# X16-Pi-Shield.net
KiCad netlist of a schematic drawn in EAGLE
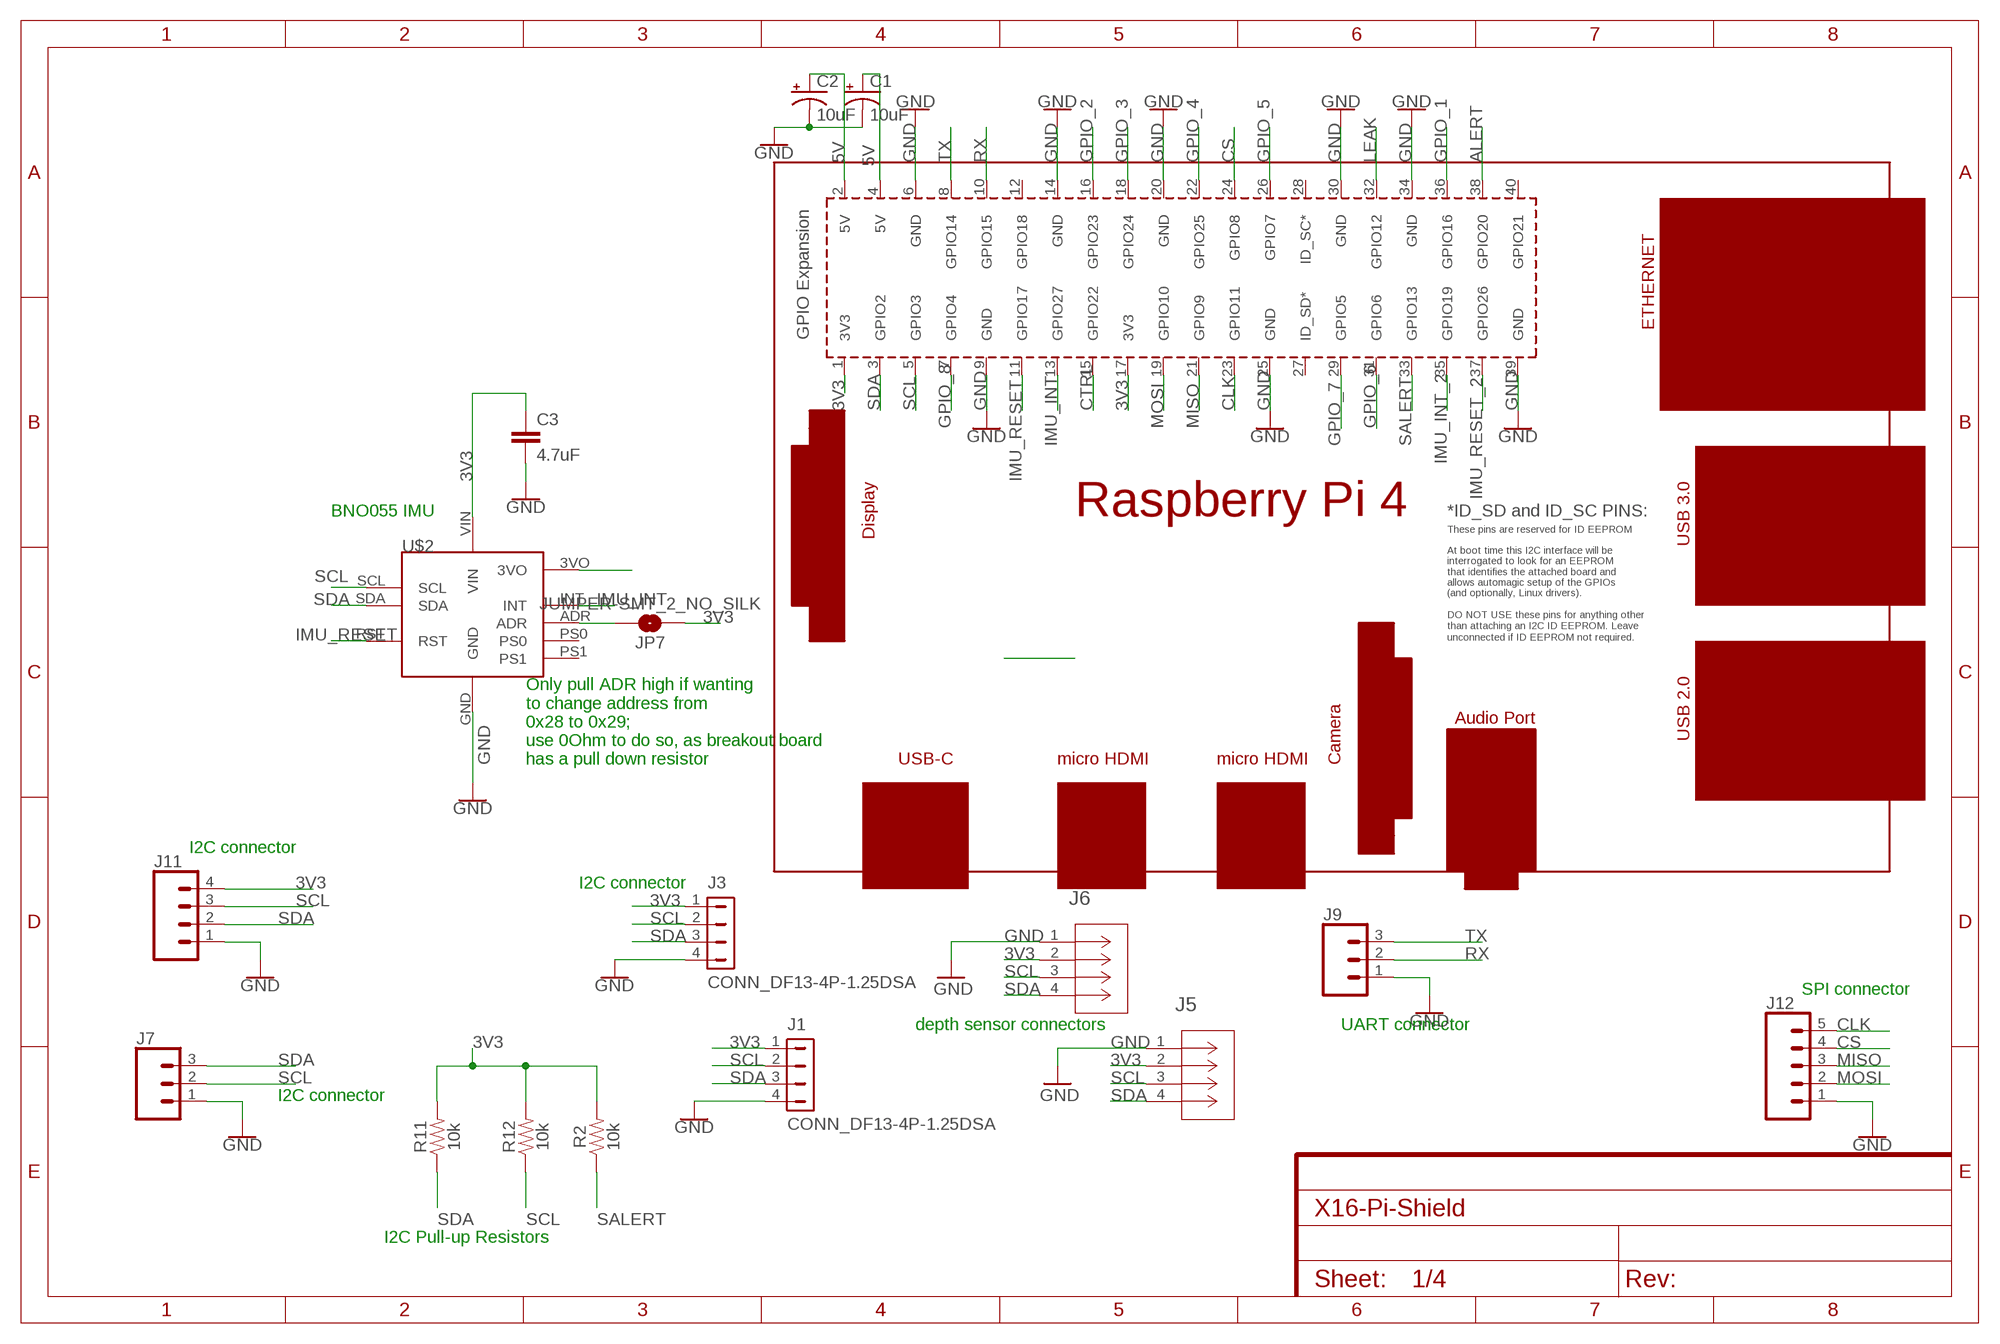
[diagram p0: schematic, sheet 1]
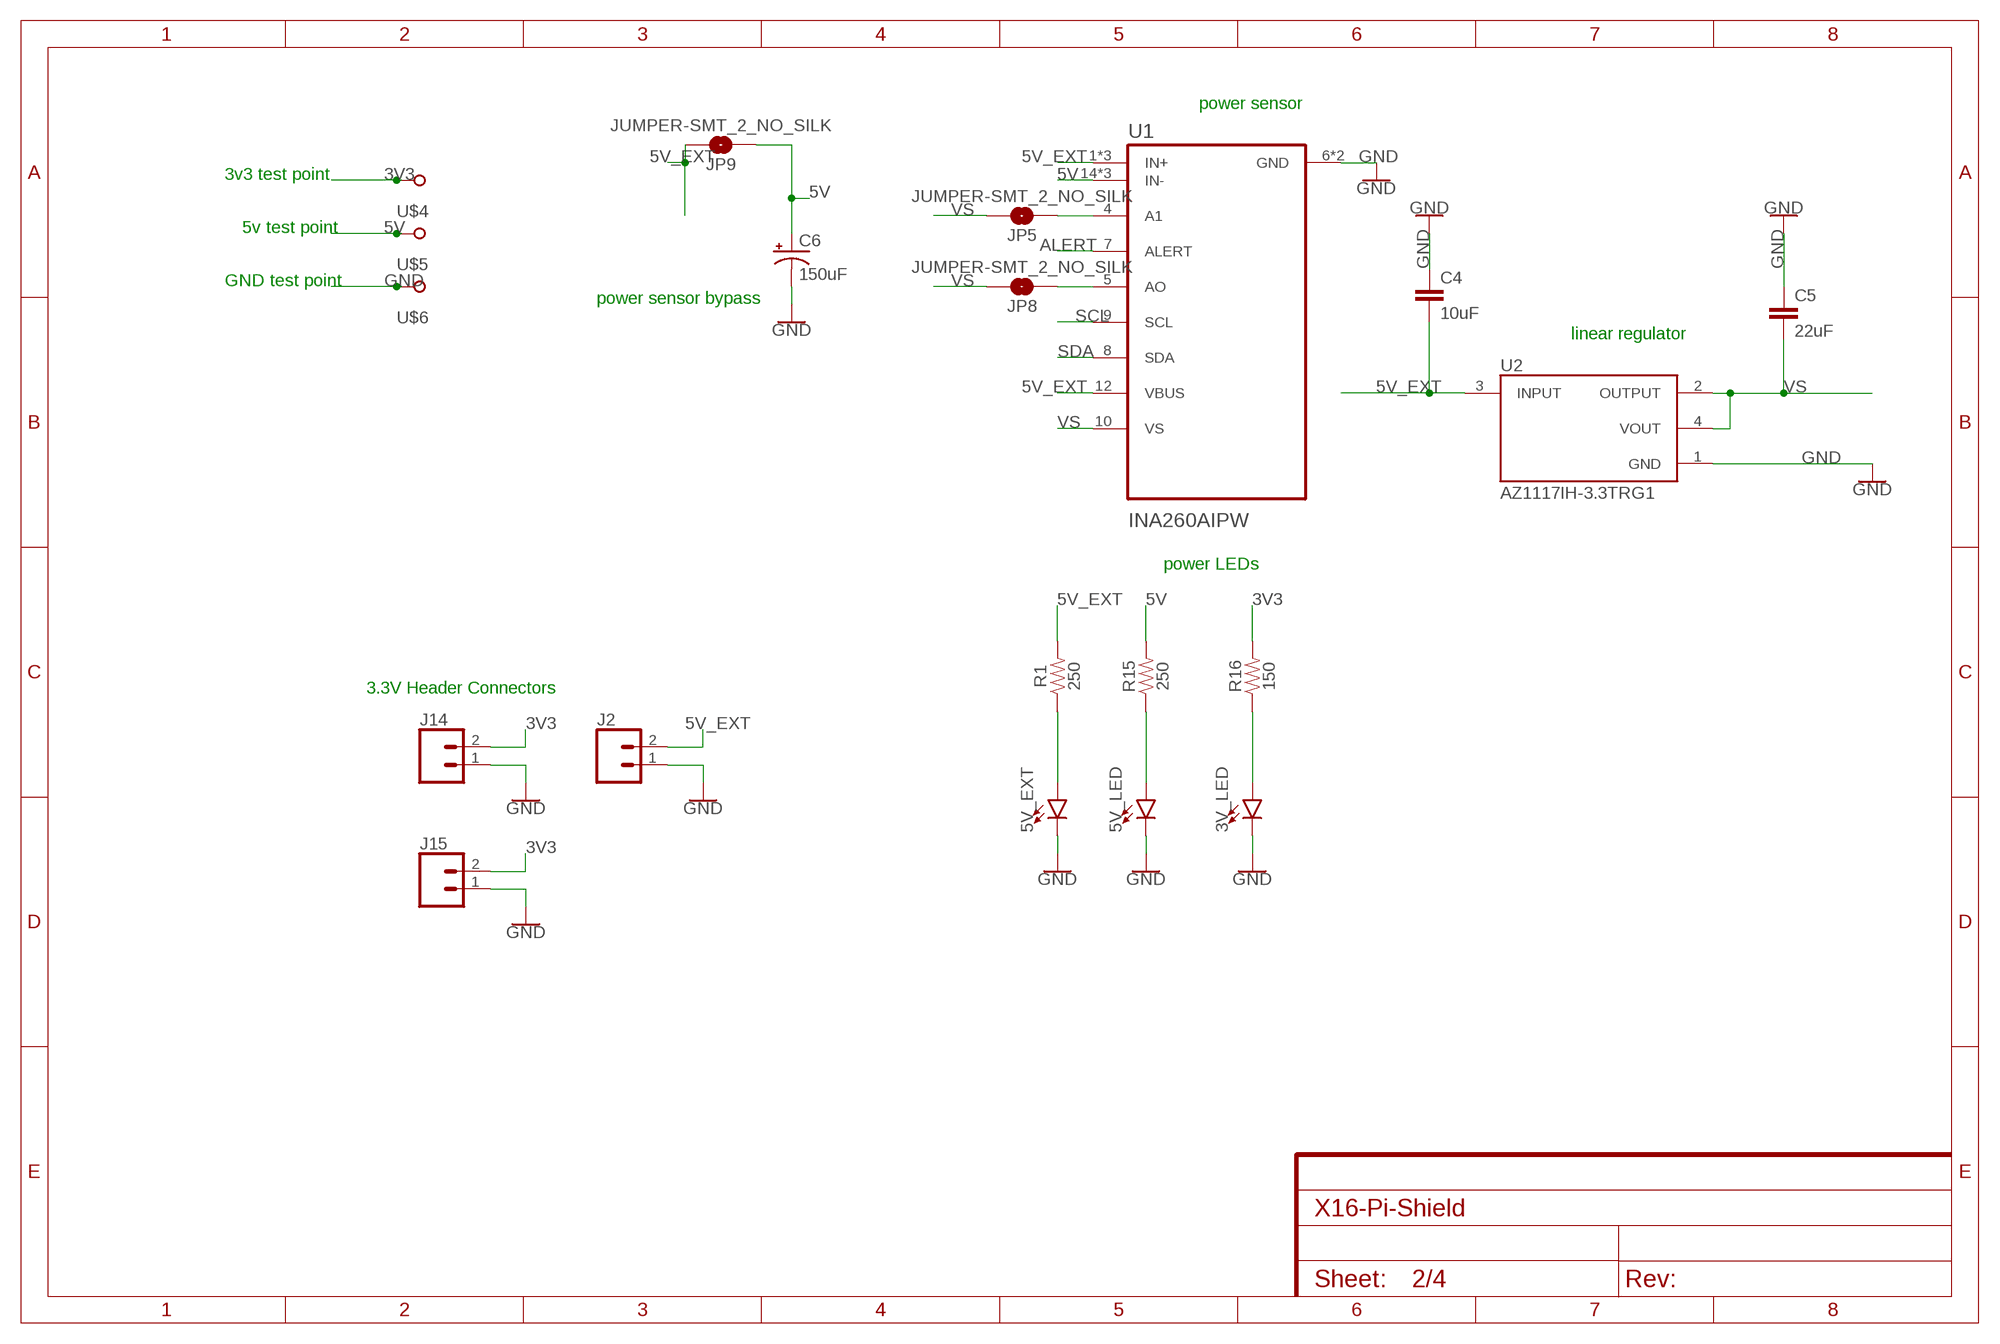
[diagram p1: schematic, sheet 2]
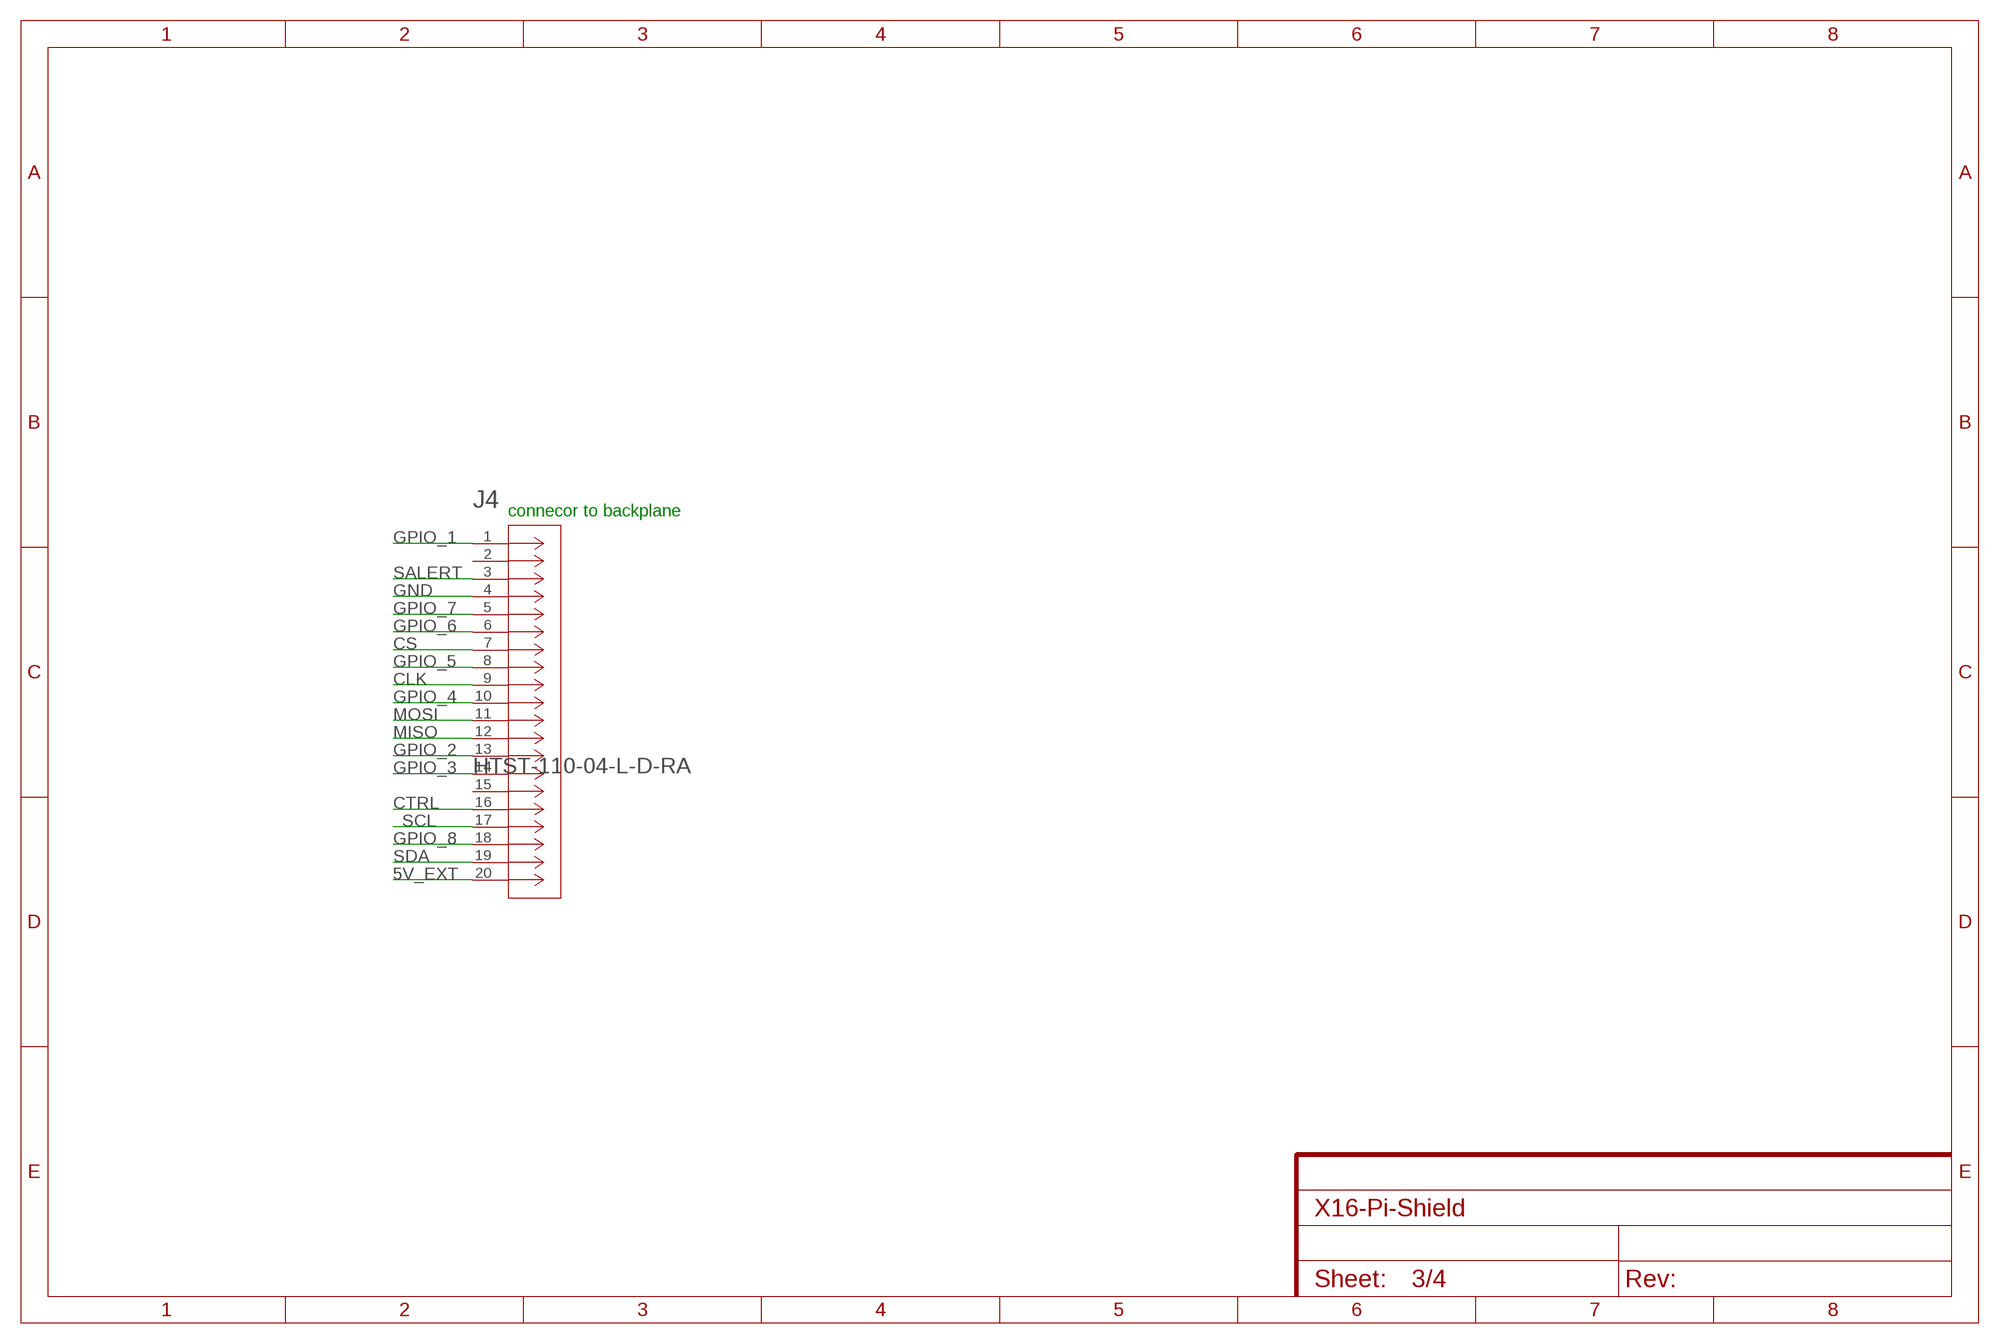
[diagram p2: schematic, sheet 3]
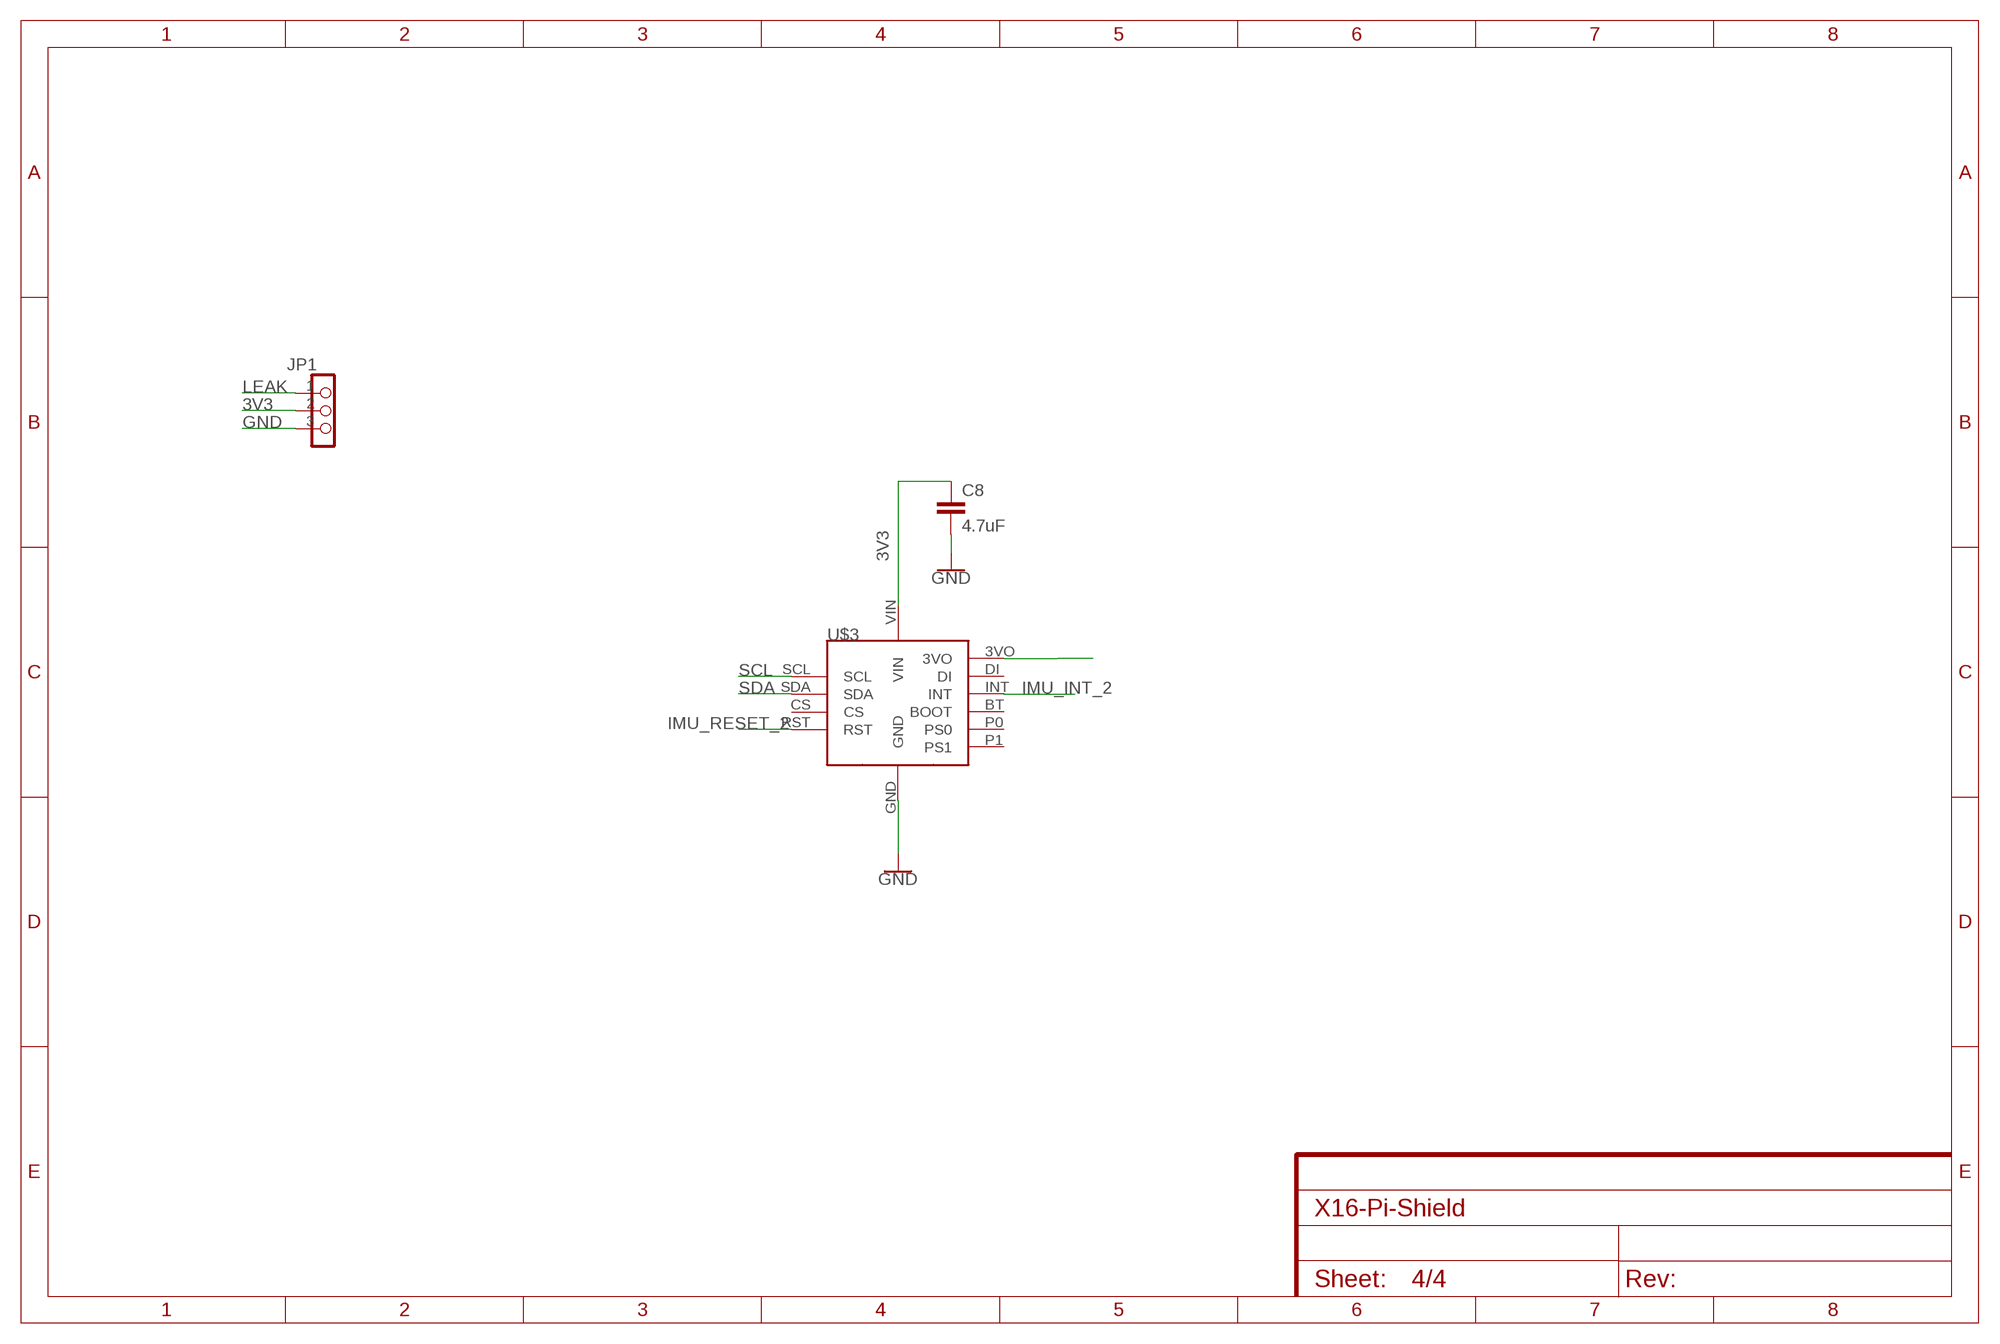
[diagram p3: schematic, sheet 4]

(export (version "E")
  (design (tool "Eeschema 10.0.6"))
  (components
    (comp (ref "J4")
      (value "HTST-110-04-L-D-RA")
      (footprint "eagle-import:CONN_HTST-110-04_05-X-D-RA_SAI")
      (fields (field (name "COPYRIGHT") "Copyright (C) 2023 Ultra Librarian. All rights reserved."))
      (libsource (lib "eagle-import") (part "HTST-110-04-L-D-RA"))
    )
    (comp (ref "C8")
      (value "4.7uF")
      (footprint "eagle-import:0603")
      (libsource (lib "eagle-import") (part "4.7UF0603"))
    )
    (comp (ref "JP1")
      (value "TEST_PIN-1X3")
      (footprint "eagle-import:1X03")
      (libsource (lib "eagle-import") (part "TEST_PIN-1X3"))
    )
    (comp (ref "U$3")
      (value "ADAFRUIT-BNO080")
      (footprint "eagle-import:ADAFRUIT-BNO080")
      (libsource (lib "eagle-import") (part "ADAFRUIT-BNO080"))
    )
    (comp (ref "3V_LED")
      (value "LEDCHIPLED_0805")
      (footprint "eagle-import:CHIPLED_0805")
      (libsource (lib "eagle-import") (part "LEDCHIPLED_0805"))
    )
    (comp (ref "5V_EXT")
      (value "LEDCHIPLED_0805")
      (footprint "eagle-import:CHIPLED_0805")
      (libsource (lib "eagle-import") (part "LEDCHIPLED_0805"))
    )
    (comp (ref "5V_LED")
      (value "LEDCHIPLED_0805")
      (footprint "eagle-import:CHIPLED_0805")
      (libsource (lib "eagle-import") (part "LEDCHIPLED_0805"))
    )
    (comp (ref "C4")
      (value "10uF")
      (footprint "eagle-import:0603")
      (libsource (lib "eagle-import") (part "2.2UF-0603-10V-20%"))
    )
    (comp (ref "C5")
      (value "22uF")
      (footprint "eagle-import:0603")
      (libsource (lib "eagle-import") (part "2.2UF-0603-10V-20%"))
    )
    (comp (ref "C6")
      (value "150uF")
      (footprint "eagle-import:2917(7343-31-METRIC)")
      (libsource (lib "eagle-import") (part "C-TANTALUM(10UF_150UF)"))
    )
    (comp (ref "J2")
      (value "CONN_02")
      (footprint "eagle-import:1X02")
      (libsource (lib "eagle-import") (part "CONN_02"))
    )
    (comp (ref "J14")
      (value "CONN_02")
      (footprint "eagle-import:1X02")
      (libsource (lib "eagle-import") (part "CONN_02"))
    )
    (comp (ref "J15")
      (value "CONN_02")
      (footprint "eagle-import:1X02")
      (libsource (lib "eagle-import") (part "CONN_02"))
    )
    (comp (ref "JP5")
      (value "JUMPER-SMT_2_NO_SILK")
      (footprint "eagle-import:SMT-JUMPER_2_NO_SILK")
      (libsource (lib "eagle-import") (part "JUMPER-SMT_2_NO_SILK"))
    )
    (comp (ref "JP8")
      (value "JUMPER-SMT_2_NO_SILK")
      (footprint "eagle-import:SMT-JUMPER_2_NO_SILK")
      (libsource (lib "eagle-import") (part "JUMPER-SMT_2_NO_SILK"))
    )
    (comp (ref "JP9")
      (value "JUMPER-SMT_2_NO_SILK")
      (footprint "eagle-import:SMT-JUMPER_2_NO_SILK")
      (libsource (lib "eagle-import") (part "JUMPER-SMT_2_NO_SILK"))
    )
    (comp (ref "R1")
      (value "250")
      (footprint "eagle-import:0603")
      (libsource (lib "eagle-import") (part "RESISTOR0603"))
    )
    (comp (ref "R15")
      (value "250")
      (footprint "eagle-import:0603")
      (libsource (lib "eagle-import") (part "RESISTOR0603"))
    )
    (comp (ref "R16")
      (value "150")
      (footprint "eagle-import:0603")
      (libsource (lib "eagle-import") (part "RESISTOR0603"))
    )
    (comp (ref "U$4")
      (value "TESTPOINT_5.04MM")
      (footprint "eagle-import:TESTPOINT_5.04MM")
      (libsource (lib "eagle-import") (part "TESTPOINT_5.04MM"))
    )
    (comp (ref "U$5")
      (value "TESTPOINT_5.04MM")
      (footprint "eagle-import:TESTPOINT_5.04MM")
      (libsource (lib "eagle-import") (part "TESTPOINT_5.04MM"))
    )
    (comp (ref "U$6")
      (value "TESTPOINT_5.04MM")
      (footprint "eagle-import:TESTPOINT_5.04MM")
      (libsource (lib "eagle-import") (part "TESTPOINT_5.04MM"))
    )
    (comp (ref "U1")
      (value "INA260AIPW")
      (footprint "eagle-import:SOP65P640X120-16N")
      (libsource (lib "eagle-import") (part "INA260AIPW"))
    )
    (comp (ref "U2")
      (value "AZ1117IH-3.3TRG1")
      (footprint "eagle-import:SOT230P700X185-4N")
      (fields (field (name "MANUFACTURER") "Diodes Inc."))
      (libsource (lib "eagle-import") (part "AZ1117IH-3.3TRG1"))
    )
    (comp (ref "C1")
      (value "10uF")
      (footprint "eagle-import:0603-POLAR")
      (libsource (lib "eagle-import") (part "10UF-POLAR-0603-6.3V-20%(TANT)"))
    )
    (comp (ref "C2")
      (value "10uF")
      (footprint "eagle-import:0603-POLAR")
      (libsource (lib "eagle-import") (part "10UF-POLAR-0603-6.3V-20%(TANT)"))
    )
    (comp (ref "C3")
      (value "4.7uF")
      (footprint "eagle-import:0603")
      (libsource (lib "eagle-import") (part "4.7UF0603"))
    )
    (comp (ref "J1")
      (value "CONN_DF13-4P-1.25DSA")
      (footprint "eagle-import:DF13-4P-1.25DSA")
      (libsource (lib "eagle-import") (part "CONN_DF13-4P-1.25DSA"))
    )
    (comp (ref "J3")
      (value "CONN_DF13-4P-1.25DSA")
      (footprint "eagle-import:DF13-4P-1.25DSA")
      (libsource (lib "eagle-import") (part "CONN_DF13-4P-1.25DSA"))
    )
    (comp (ref "J5")
      (value "BM04B-GHS-TBT")
      (footprint "eagle-import:CONN_BM04B-GHS-TBT_JST")
      (fields (field (name "COPYRIGHT") "Copyright (C) 2023 Ultra Librarian. All rights reserved."))
      (libsource (lib "eagle-import") (part "BM04B-GHS-TBT"))
    )
    (comp (ref "J6")
      (value "BM04B-GHS-TBT")
      (footprint "eagle-import:CONN_BM04B-GHS-TBT_JST")
      (fields (field (name "COPYRIGHT") "Copyright (C) 2023 Ultra Librarian. All rights reserved."))
      (libsource (lib "eagle-import") (part "BM04B-GHS-TBT"))
    )
    (comp (ref "J7")
      (value "CONN_03")
      (footprint "eagle-import:1X03")
      (libsource (lib "eagle-import") (part "CONN_03"))
    )
    (comp (ref "J9")
      (value "CONN_03")
      (footprint "eagle-import:1X03")
      (libsource (lib "eagle-import") (part "CONN_03"))
    )
    (comp (ref "J11")
      (value "CONN_04")
      (footprint "eagle-import:1X04")
      (libsource (lib "eagle-import") (part "CONN_04"))
    )
    (comp (ref "J12")
      (value "CONN_05")
      (footprint "eagle-import:1X05")
      (libsource (lib "eagle-import") (part "CONN_05"))
    )
    (comp (ref "JP7")
      (value "JUMPER-SMT_2_NO_SILK")
      (footprint "eagle-import:SMT-JUMPER_2_NO_SILK")
      (libsource (lib "eagle-import") (part "JUMPER-SMT_2_NO_SILK"))
    )
    (comp (ref "R2")
      (value "10k")
      (footprint "eagle-import:0603")
      (libsource (lib "eagle-import") (part "RESISTOR0603"))
    )
    (comp (ref "R11")
      (value "10k")
      (footprint "eagle-import:0603")
      (libsource (lib "eagle-import") (part "RESISTOR0603"))
    )
    (comp (ref "R12")
      (value "10k")
      (footprint "eagle-import:0603")
      (libsource (lib "eagle-import") (part "RESISTOR0603"))
    )
    (comp (ref "U$1")
      (value "RPI4")
      (footprint "eagle-import:RPI4")
      (libsource (lib "eagle-import") (part "RPI4"))
    )
    (comp (ref "U$2")
      (value "CONN_ADAFRUIT-BNO055")
      (footprint "eagle-import:ADAFRUIT-BNO055")
      (libsource (lib "eagle-import") (part "CONN_ADAFRUIT-BNO055"))
    )
  )
  (nets
    (net (code "1") (name "3V3") (class "Default")
      (node (ref "C3") (pin "1") (pinfunction "1_1") (pintype "passive"))
      (node (ref "C8") (pin "1") (pinfunction "1_1") (pintype "passive"))
      (node (ref "J1") (pin "1") (pinfunction "1_1") (pintype "passive"))
      (node (ref "J11") (pin "4") (pinfunction "4_4") (pintype "passive"))
      (node (ref "J14") (pin "2") (pinfunction "2_2") (pintype "passive"))
      (node (ref "J15") (pin "2") (pinfunction "2_2") (pintype "passive"))
      (node (ref "J3") (pin "1") (pinfunction "1_1") (pintype "passive"))
      (node (ref "J5") (pin "2") (pinfunction "2_2") (pintype "passive"))
      (node (ref "J6") (pin "2") (pinfunction "2_2") (pintype "passive"))
      (node (ref "JP1") (pin "2") (pinfunction "2_2") (pintype "passive"))
      (node (ref "JP7") (pin "1") (pinfunction "1_1") (pintype "passive"))
      (node (ref "R11") (pin "2") (pinfunction "2_2") (pintype "passive"))
      (node (ref "R12") (pin "2") (pinfunction "2_2") (pintype "passive"))
      (node (ref "R16") (pin "2") (pinfunction "2_2") (pintype "passive"))
      (node (ref "R2") (pin "2") (pinfunction "2_2") (pintype "passive"))
      (node (ref "U$1") (pin "1") (pinfunction "3V3_1") (pintype "bidirectional"))
      (node (ref "U$1") (pin "17") (pinfunction "3V3_17") (pintype "bidirectional"))
      (node (ref "U$2") (pin "VIN") (pinfunction "VIN_VIN") (pintype "power_in"))
      (node (ref "U$3") (pin "VIN") (pinfunction "VIN_VIN") (pintype "power_in"))
      (node (ref "U$4") (pin "TP") (pinfunction "TP_TP") (pintype "input"))
    )
    (net (code "2") (name "5V") (class "Default")
      (node (ref "C1") (pin "+") (pinfunction "+_+") (pintype "passive"))
      (node (ref "C2") (pin "+") (pinfunction "+_+") (pintype "passive"))
      (node (ref "C6") (pin "+") (pinfunction "+_+") (pintype "passive"))
      (node (ref "JP9") (pin "1") (pinfunction "1_1") (pintype "passive"))
      (node (ref "R15") (pin "2") (pinfunction "2_2") (pintype "passive"))
      (node (ref "U$1") (pin "2") (pinfunction "5V_2") (pintype "bidirectional"))
      (node (ref "U$1") (pin "4") (pinfunction "5V_4") (pintype "bidirectional"))
      (node (ref "U$5") (pin "TP") (pinfunction "TP_TP") (pintype "input"))
      (node (ref "U1") (pin "14") (pinfunction "IN-_14") (pintype "input"))
      (node (ref "U1") (pin "15") (pinfunction "IN-_15") (pintype "input"))
      (node (ref "U1") (pin "16") (pinfunction "IN-_16") (pintype "input"))
    )
    (net (code "3") (name "5V_EXT") (class "Default")
      (node (ref "C4") (pin "2") (pinfunction "2_2") (pintype "passive"))
      (node (ref "J2") (pin "2") (pinfunction "2_2") (pintype "passive"))
      (node (ref "J4") (pin "20") (pinfunction "20_20") (pintype "passive"))
      (node (ref "JP9") (pin "2") (pinfunction "2_2") (pintype "passive"))
      (node (ref "R1") (pin "2") (pinfunction "2_2") (pintype "passive"))
      (node (ref "U1") (pin "1") (pinfunction "IN+_1") (pintype "input"))
      (node (ref "U1") (pin "12") (pinfunction "VBUS_12") (pintype "bidirectional"))
      (node (ref "U1") (pin "2") (pinfunction "IN+_2") (pintype "input"))
      (node (ref "U1") (pin "3") (pinfunction "IN+_3") (pintype "input"))
      (node (ref "U2") (pin "3") (pinfunction "INPUT_3") (pintype "input"))
    )
    (net (code "4") (name "ALERT") (class "Default")
      (node (ref "U$1") (pin "38") (pinfunction "GPIO20_38") (pintype "bidirectional"))
      (node (ref "U1") (pin "7") (pinfunction "ALERT_7") (pintype "bidirectional"))
    )
    (net (code "5") (name "CLK") (class "Default")
      (node (ref "J12") (pin "5") (pinfunction "5_5") (pintype "passive"))
      (node (ref "J4") (pin "9") (pinfunction "9_9") (pintype "passive"))
      (node (ref "U$1") (pin "23") (pinfunction "GPIO11_23") (pintype "bidirectional"))
    )
    (net (code "6") (name "CS") (class "Default")
      (node (ref "J12") (pin "4") (pinfunction "4_4") (pintype "passive"))
      (node (ref "J4") (pin "7") (pinfunction "7_7") (pintype "passive"))
      (node (ref "U$1") (pin "24") (pinfunction "GPIO8_24") (pintype "bidirectional"))
    )
    (net (code "7") (name "CTRL") (class "Default")
      (node (ref "J4") (pin "16") (pinfunction "16_16") (pintype "passive"))
      (node (ref "U$1") (pin "15") (pinfunction "GPIO22_15") (pintype "bidirectional"))
    )
    (net (code "8") (name "GND") (class "Default")
      (node (ref "3V_LED") (pin "C") (pinfunction "C_C") (pintype "passive"))
      (node (ref "5V_EXT") (pin "C") (pinfunction "C_C") (pintype "passive"))
      (node (ref "5V_LED") (pin "C") (pinfunction "C_C") (pintype "passive"))
      (node (ref "C1") (pin "-") (pinfunction "-_-") (pintype "passive"))
      (node (ref "C2") (pin "-") (pinfunction "-_-") (pintype "passive"))
      (node (ref "C3") (pin "2") (pinfunction "2_2") (pintype "passive"))
      (node (ref "C4") (pin "1") (pinfunction "1_1") (pintype "passive"))
      (node (ref "C5") (pin "1") (pinfunction "1_1") (pintype "passive"))
      (node (ref "C6") (pin "-") (pinfunction "-_-") (pintype "passive"))
      (node (ref "C8") (pin "2") (pinfunction "2_2") (pintype "passive"))
      (node (ref "J1") (pin "4") (pinfunction "4_4") (pintype "passive"))
      (node (ref "J11") (pin "1") (pinfunction "1_1") (pintype "passive"))
      (node (ref "J12") (pin "1") (pinfunction "1_1") (pintype "passive"))
      (node (ref "J14") (pin "1") (pinfunction "1_1") (pintype "passive"))
      (node (ref "J15") (pin "1") (pinfunction "1_1") (pintype "passive"))
      (node (ref "J2") (pin "1") (pinfunction "1_1") (pintype "passive"))
      (node (ref "J3") (pin "4") (pinfunction "4_4") (pintype "passive"))
      (node (ref "J4") (pin "4") (pinfunction "4_4") (pintype "passive"))
      (node (ref "J5") (pin "1") (pinfunction "1_1") (pintype "passive"))
      (node (ref "J6") (pin "1") (pinfunction "1_1") (pintype "passive"))
      (node (ref "J7") (pin "1") (pinfunction "1_1") (pintype "passive"))
      (node (ref "J9") (pin "1") (pinfunction "1_1") (pintype "passive"))
      (node (ref "JP1") (pin "3") (pinfunction "3_3") (pintype "passive"))
      (node (ref "U$1") (pin "14") (pinfunction "GND_14") (pintype "bidirectional"))
      (node (ref "U$1") (pin "20") (pinfunction "GND_20") (pintype "bidirectional"))
      (node (ref "U$1") (pin "25") (pinfunction "GND_25") (pintype "bidirectional"))
      (node (ref "U$1") (pin "30") (pinfunction "GND_30") (pintype "bidirectional"))
      (node (ref "U$1") (pin "34") (pinfunction "GND_34") (pintype "bidirectional"))
      (node (ref "U$1") (pin "39") (pinfunction "GND_39") (pintype "bidirectional"))
      (node (ref "U$1") (pin "6") (pinfunction "GND_6") (pintype "bidirectional"))
      (node (ref "U$1") (pin "9") (pinfunction "GND_9") (pintype "bidirectional"))
      (node (ref "U$2") (pin "GND") (pinfunction "GND_GND") (pintype "power_in"))
      (node (ref "U$3") (pin "GND") (pinfunction "GND_GND") (pintype "power_in"))
      (node (ref "U$6") (pin "TP") (pinfunction "TP_TP") (pintype "input"))
      (node (ref "U1") (pin "11") (pinfunction "GND_11") (pintype "power_in"))
      (node (ref "U1") (pin "6") (pinfunction "GND_6") (pintype "power_in"))
      (node (ref "U2") (pin "1") (pinfunction "GND_1") (pintype "power_in"))
    )
    (net (code "9") (name "GPIO_1") (class "Default")
      (node (ref "J4") (pin "1") (pinfunction "1_1") (pintype "passive"))
      (node (ref "U$1") (pin "36") (pinfunction "GPIO16_36") (pintype "bidirectional"))
    )
    (net (code "10") (name "GPIO_2") (class "Default")
      (node (ref "J4") (pin "13") (pinfunction "13_13") (pintype "passive"))
      (node (ref "U$1") (pin "16") (pinfunction "GPIO23_16") (pintype "bidirectional"))
    )
    (net (code "11") (name "GPIO_3") (class "Default")
      (node (ref "J4") (pin "14") (pinfunction "14_14") (pintype "passive"))
      (node (ref "U$1") (pin "18") (pinfunction "GPIO24_18") (pintype "bidirectional"))
    )
    (net (code "12") (name "GPIO_4") (class "Default")
      (node (ref "J4") (pin "10") (pinfunction "10_10") (pintype "passive"))
      (node (ref "U$1") (pin "22") (pinfunction "GPIO25_22") (pintype "bidirectional"))
    )
    (net (code "13") (name "GPIO_5") (class "Default")
      (node (ref "J4") (pin "8") (pinfunction "8_8") (pintype "passive"))
      (node (ref "U$1") (pin "26") (pinfunction "GPIO7_26") (pintype "bidirectional"))
    )
    (net (code "14") (name "GPIO_6") (class "Default")
      (node (ref "J4") (pin "6") (pinfunction "6_6") (pintype "passive"))
      (node (ref "U$1") (pin "31") (pinfunction "GPIO6_31") (pintype "bidirectional"))
    )
    (net (code "15") (name "GPIO_7") (class "Default")
      (node (ref "J4") (pin "5") (pinfunction "5_5") (pintype "passive"))
      (node (ref "U$1") (pin "29") (pinfunction "GPIO5_29") (pintype "bidirectional"))
    )
    (net (code "16") (name "GPIO_8") (class "Default")
      (node (ref "J4") (pin "18") (pinfunction "18_18") (pintype "passive"))
      (node (ref "U$1") (pin "7") (pinfunction "GPIO4_7") (pintype "bidirectional"))
    )
    (net (code "17") (name "IMU_INT") (class "Default")
      (node (ref "U$1") (pin "13") (pinfunction "GPIO27_13") (pintype "bidirectional"))
      (node (ref "U$2") (pin "INT") (pinfunction "INT_INT") (pintype "output"))
    )
    (net (code "18") (name "IMU_INT_2") (class "Default")
      (node (ref "U$1") (pin "35") (pinfunction "GPIO19_35") (pintype "bidirectional"))
      (node (ref "U$3") (pin "INT") (pinfunction "INT_INT") (pintype "output"))
    )
    (net (code "19") (name "IMU_RESET") (class "Default")
      (node (ref "U$1") (pin "11") (pinfunction "GPIO17_11") (pintype "bidirectional"))
      (node (ref "U$2") (pin "RST") (pinfunction "RST_RST") (pintype "input"))
    )
    (net (code "20") (name "IMU_RESET_2") (class "Default")
      (node (ref "U$1") (pin "37") (pinfunction "GPIO26_37") (pintype "bidirectional"))
      (node (ref "U$3") (pin "RST") (pinfunction "RST_RST") (pintype "input"))
    )
    (net (code "21") (name "LEAK") (class "Default")
      (node (ref "JP1") (pin "1") (pinfunction "1_1") (pintype "passive"))
      (node (ref "U$1") (pin "32") (pinfunction "GPIO12_32") (pintype "bidirectional"))
    )
    (net (code "22") (name "MISO") (class "Default")
      (node (ref "J12") (pin "3") (pinfunction "3_3") (pintype "passive"))
      (node (ref "J4") (pin "12") (pinfunction "12_12") (pintype "passive"))
      (node (ref "U$1") (pin "21") (pinfunction "GPIO9_21") (pintype "bidirectional"))
    )
    (net (code "23") (name "MOSI") (class "Default")
      (node (ref "J12") (pin "2") (pinfunction "2_2") (pintype "passive"))
      (node (ref "J4") (pin "11") (pinfunction "11_11") (pintype "passive"))
      (node (ref "U$1") (pin "19") (pinfunction "GPIO10_19") (pintype "bidirectional"))
    )
    (net (code "24") (name "Net-(3V_LED-PadA)") (class "Default")
      (node (ref "3V_LED") (pin "A") (pinfunction "A_A") (pintype "passive"))
      (node (ref "R16") (pin "1") (pinfunction "1_1") (pintype "passive"))
    )
    (net (code "25") (name "Net-(5V_EXT-PadA)") (class "Default")
      (node (ref "5V_EXT") (pin "A") (pinfunction "A_A") (pintype "passive"))
      (node (ref "R1") (pin "1") (pinfunction "1_1") (pintype "passive"))
    )
    (net (code "26") (name "Net-(5V_LED-PadA)") (class "Default")
      (node (ref "5V_LED") (pin "A") (pinfunction "A_A") (pintype "passive"))
      (node (ref "R15") (pin "1") (pinfunction "1_1") (pintype "passive"))
    )
    (net (code "27") (name "Net-(JP7-Pad2)") (class "Default")
      (node (ref "JP7") (pin "2") (pinfunction "2_2") (pintype "passive"))
      (node (ref "U$2") (pin "ADR") (pinfunction "ADR_ADR") (pintype "input"))
    )
    (net (code "28") (name "Net-(U1-A1)") (class "Default")
      (node (ref "JP5") (pin "1") (pinfunction "1_1") (pintype "passive"))
      (node (ref "U1") (pin "4") (pinfunction "A1_4") (pintype "bidirectional"))
    )
    (net (code "29") (name "Net-(U1-AO)") (class "Default")
      (node (ref "JP8") (pin "1") (pinfunction "1_1") (pintype "passive"))
      (node (ref "U1") (pin "5") (pinfunction "AO_5") (pintype "bidirectional"))
    )
    (net (code "30") (name "RX") (class "Default")
      (node (ref "J9") (pin "2") (pinfunction "2_2") (pintype "passive"))
      (node (ref "U$1") (pin "10") (pinfunction "GPIO15_10") (pintype "bidirectional"))
    )
    (net (code "31") (name "SALERT") (class "Default")
      (node (ref "J4") (pin "3") (pinfunction "3_3") (pintype "passive"))
      (node (ref "R2") (pin "1") (pinfunction "1_1") (pintype "passive"))
      (node (ref "U$1") (pin "33") (pinfunction "GPIO13_33") (pintype "bidirectional"))
    )
    (net (code "32") (name "SCL") (class "Default")
      (node (ref "J1") (pin "2") (pinfunction "2_2") (pintype "passive"))
      (node (ref "J11") (pin "3") (pinfunction "3_3") (pintype "passive"))
      (node (ref "J3") (pin "2") (pinfunction "2_2") (pintype "passive"))
      (node (ref "J4") (pin "17") (pinfunction "17_17") (pintype "passive"))
      (node (ref "J5") (pin "3") (pinfunction "3_3") (pintype "passive"))
      (node (ref "J6") (pin "3") (pinfunction "3_3") (pintype "passive"))
      (node (ref "J7") (pin "2") (pinfunction "2_2") (pintype "passive"))
      (node (ref "R12") (pin "1") (pinfunction "1_1") (pintype "passive"))
      (node (ref "U$1") (pin "5") (pinfunction "GPIO3_5") (pintype "bidirectional"))
      (node (ref "U$2") (pin "SCL") (pinfunction "SCL_SCL") (pintype "bidirectional"))
      (node (ref "U$3") (pin "SCL") (pinfunction "SCL_SCL") (pintype "bidirectional"))
      (node (ref "U1") (pin "9") (pinfunction "SCL_9") (pintype "bidirectional"))
    )
    (net (code "33") (name "SDA") (class "Default")
      (node (ref "J1") (pin "3") (pinfunction "3_3") (pintype "passive"))
      (node (ref "J11") (pin "2") (pinfunction "2_2") (pintype "passive"))
      (node (ref "J3") (pin "3") (pinfunction "3_3") (pintype "passive"))
      (node (ref "J4") (pin "19") (pinfunction "19_19") (pintype "passive"))
      (node (ref "J5") (pin "4") (pinfunction "4_4") (pintype "passive"))
      (node (ref "J6") (pin "4") (pinfunction "4_4") (pintype "passive"))
      (node (ref "J7") (pin "3") (pinfunction "3_3") (pintype "passive"))
      (node (ref "R11") (pin "1") (pinfunction "1_1") (pintype "passive"))
      (node (ref "U$1") (pin "3") (pinfunction "GPIO2_3") (pintype "bidirectional"))
      (node (ref "U$2") (pin "SDA") (pinfunction "SDA_SDA") (pintype "bidirectional"))
      (node (ref "U$3") (pin "SDA") (pinfunction "SDA_SDA") (pintype "bidirectional"))
      (node (ref "U1") (pin "8") (pinfunction "SDA_8") (pintype "bidirectional"))
    )
    (net (code "34") (name "TX") (class "Default")
      (node (ref "J9") (pin "3") (pinfunction "3_3") (pintype "passive"))
      (node (ref "U$1") (pin "8") (pinfunction "GPIO14_8") (pintype "bidirectional"))
    )
    (net (code "35") (name "VS") (class "Default")
      (node (ref "C5") (pin "2") (pinfunction "2_2") (pintype "passive"))
      (node (ref "JP5") (pin "2") (pinfunction "2_2") (pintype "passive"))
      (node (ref "JP8") (pin "2") (pinfunction "2_2") (pintype "passive"))
      (node (ref "U1") (pin "10") (pinfunction "VS_10") (pintype "bidirectional"))
      (node (ref "U2") (pin "2") (pinfunction "OUTPUT_2") (pintype "output"))
      (node (ref "U2") (pin "4") (pinfunction "VOUT_4") (pintype "output"))
    )
    (net (code "36") (name "unconnected-(J4-Pad2)") (class "Default")
      (node (ref "J4") (pin "2") (pinfunction "2_2") (pintype "passive"))
    )
    (net (code "37") (name "unconnected-(J4-Pad15)") (class "Default")
      (node (ref "J4") (pin "15") (pinfunction "15_15") (pintype "passive"))
    )
    (net (code "38") (name "unconnected-(U$1-GPIO18-Pad12)") (class "Default")
      (node (ref "U$1") (pin "12") (pinfunction "GPIO18_12") (pintype "bidirectional"))
    )
    (net (code "39") (name "unconnected-(U$1-GPIO21-Pad40)") (class "Default")
      (node (ref "U$1") (pin "40") (pinfunction "GPIO21_40") (pintype "bidirectional"))
    )
    (net (code "40") (name "unconnected-(U$1-ID_SC*-Pad28)") (class "Default")
      (node (ref "U$1") (pin "28") (pinfunction "ID_SC*_28") (pintype "bidirectional"))
    )
    (net (code "41") (name "unconnected-(U$1-ID_SD*-Pad27)") (class "Default")
      (node (ref "U$1") (pin "27") (pinfunction "ID_SD*_27") (pintype "bidirectional"))
    )
    (net (code "42") (name "unconnected-(U$2-Pad3VO)") (class "Default")
      (node (ref "U$2") (pin "3VO") (pinfunction "3VO_3VO") (pintype "power_in"))
    )
    (net (code "43") (name "unconnected-(U$2-PadPS0)") (class "Default")
      (node (ref "U$2") (pin "PS0") (pinfunction "PS0_PS0") (pintype "input"))
    )
    (net (code "44") (name "unconnected-(U$2-PadPS1)") (class "Default")
      (node (ref "U$2") (pin "PS1") (pinfunction "PS1_PS1") (pintype "input"))
    )
    (net (code "45") (name "unconnected-(U$3-BOOT-PadBT)") (class "Default")
      (node (ref "U$3") (pin "BT") (pinfunction "BOOT_BT") (pintype "bidirectional"))
    )
    (net (code "46") (name "unconnected-(U$3-PS0-PadP0)") (class "Default")
      (node (ref "U$3") (pin "P0") (pinfunction "PS0_P0") (pintype "input"))
    )
    (net (code "47") (name "unconnected-(U$3-PS1-PadP1)") (class "Default")
      (node (ref "U$3") (pin "P1") (pinfunction "PS1_P1") (pintype "input"))
    )
    (net (code "48") (name "unconnected-(U$3-Pad3VO)") (class "Default")
      (node (ref "U$3") (pin "3VO") (pinfunction "3VO_3VO") (pintype "power_in"))
    )
    (net (code "49") (name "unconnected-(U$3-PadCS)") (class "Default")
      (node (ref "U$3") (pin "CS") (pinfunction "CS_CS") (pintype "bidirectional"))
    )
    (net (code "50") (name "unconnected-(U$3-PadDI)") (class "Default")
      (node (ref "U$3") (pin "DI") (pinfunction "DI_DI") (pintype "bidirectional"))
    )
  )
)
